# attiny85.net
KiCad netlist of a schematic drawn in EAGLE
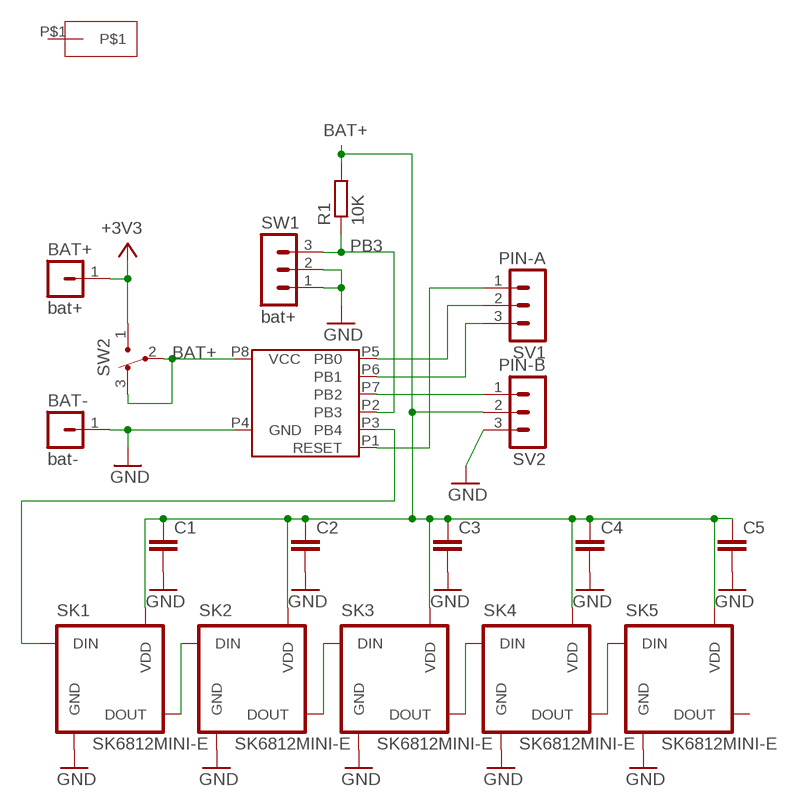
[diagram p0: schematic, sheet 1]

(export (version "E")
  (design (tool "Eeschema 10.0.6"))
  (components
    (comp (ref "ATTINY85-1")
      (value "ATTINY85")
      (footprint "eagle-import:ATTINY85-20SUR")
      (libsource (lib "eagle-import") (part "ATTINY85SOP8"))
    )
    (comp (ref "BAT+")
      (value "bat+")
      (footprint "eagle-import:PINHEAD-MA01-1")
      (libsource (lib "eagle-import") (part "PINHEAD-MA01-1"))
    )
    (comp (ref "BAT-")
      (value "bat-")
      (footprint "eagle-import:PINHEAD-MA01-1")
      (libsource (lib "eagle-import") (part "PINHEAD-MA01-1"))
    )
    (comp (ref "C1")
      (value "C-EUC2012")
      (footprint "eagle-import:C2012")
      (libsource (lib "eagle-import") (part "C-EUC2012"))
    )
    (comp (ref "C2")
      (value "C-EUC2012")
      (footprint "eagle-import:C2012")
      (libsource (lib "eagle-import") (part "C-EUC2012"))
    )
    (comp (ref "C3")
      (value "C-EUC2012")
      (footprint "eagle-import:C2012")
      (libsource (lib "eagle-import") (part "C-EUC2012"))
    )
    (comp (ref "C4")
      (value "C-EUC2012")
      (footprint "eagle-import:C2012")
      (libsource (lib "eagle-import") (part "C-EUC2012"))
    )
    (comp (ref "C5")
      (value "C-EUC2012")
      (footprint "eagle-import:C2012")
      (libsource (lib "eagle-import") (part "C-EUC2012"))
    )
    (comp (ref "PAD33")
      (value "PAD150X50")
      (footprint "eagle-import:PAD5X15")
      (libsource (lib "eagle-import") (part "PAD150X50"))
    )
    (comp (ref "R1")
      (value "10K")
      (footprint "eagle-import:M3216")
      (libsource (lib "eagle-import") (part "R-EU_M3216"))
    )
    (comp (ref "SK1")
      (value "SK6812MINI-E")
      (footprint "eagle-import:SK6812MINI-E")
      (libsource (lib "eagle-import") (part "SK6812MINI-E"))
    )
    (comp (ref "SK2")
      (value "SK6812MINI-E")
      (footprint "eagle-import:SK6812MINI-E")
      (libsource (lib "eagle-import") (part "SK6812MINI-E"))
    )
    (comp (ref "SK3")
      (value "SK6812MINI-E")
      (footprint "eagle-import:SK6812MINI-E")
      (libsource (lib "eagle-import") (part "SK6812MINI-E"))
    )
    (comp (ref "SK4")
      (value "SK6812MINI-E")
      (footprint "eagle-import:SK6812MINI-E")
      (libsource (lib "eagle-import") (part "SK6812MINI-E"))
    )
    (comp (ref "SK5")
      (value "SK6812MINI-E")
      (footprint "eagle-import:SK6812MINI-E")
      (libsource (lib "eagle-import") (part "SK6812MINI-E"))
    )
    (comp (ref "SV1")
      (value "PIN-A")
      (footprint "eagle-import:PINHEAD-MA03-1")
      (libsource (lib "eagle-import") (part "PINHEAD-MA03-1"))
    )
    (comp (ref "SV2")
      (value "PIN-B")
      (footprint "eagle-import:PINHEAD-MA03-1")
      (libsource (lib "eagle-import") (part "PINHEAD-MA03-1"))
    )
    (comp (ref "SW1")
      (value "bat+")
      (footprint "eagle-import:PINHEAD-MA03-1")
      (libsource (lib "eagle-import") (part "PINHEAD-MA03-1"))
    )
    (comp (ref "SW2")
      (value "POWER")
      (footprint "eagle-import:SW3-1")
      (fields (field (name "MF") "HiLetgo"))
      (libsource (lib "eagle-import") (part "SW3-1"))
    )
  )
  (nets
    (net (code "1") (name "+3V3") (class "Default")
      (node (ref "BAT+") (pin "1") (pinfunction "1_1") (pintype "passive"))
      (node (ref "SW2") (pin "1") (pinfunction "1_1") (pintype "passive"))
    )
    (net (code "2") (name "/BAT+") (class "Default")
      (node (ref "ATTINY85-1") (pin "P8") (pinfunction "VCC_P8") (pintype "bidirectional"))
      (node (ref "C1") (pin "1") (pinfunction "1_1") (pintype "passive"))
      (node (ref "C2") (pin "1") (pinfunction "1_1") (pintype "passive"))
      (node (ref "C3") (pin "1") (pinfunction "1_1") (pintype "passive"))
      (node (ref "C4") (pin "1") (pinfunction "1_1") (pintype "passive"))
      (node (ref "C5") (pin "1") (pinfunction "1_1") (pintype "passive"))
      (node (ref "R1") (pin "2") (pinfunction "2_2") (pintype "passive"))
      (node (ref "SK1") (pin "VDD") (pinfunction "VDD_VDD") (pintype "bidirectional"))
      (node (ref "SK2") (pin "VDD") (pinfunction "VDD_VDD") (pintype "bidirectional"))
      (node (ref "SK3") (pin "VDD") (pinfunction "VDD_VDD") (pintype "bidirectional"))
      (node (ref "SK4") (pin "VDD") (pinfunction "VDD_VDD") (pintype "bidirectional"))
      (node (ref "SK5") (pin "VDD") (pinfunction "VDD_VDD") (pintype "bidirectional"))
      (node (ref "SV2") (pin "2") (pinfunction "2_2") (pintype "passive"))
      (node (ref "SW2") (pin "2") (pinfunction "2_2") (pintype "passive"))
      (node (ref "SW2") (pin "3") (pinfunction "3_3") (pintype "passive"))
    )
    (net (code "3") (name "/PB3") (class "Default")
      (node (ref "ATTINY85-1") (pin "P2") (pinfunction "PB3_P2") (pintype "bidirectional"))
      (node (ref "R1") (pin "1") (pinfunction "1_1") (pintype "passive"))
      (node (ref "SW1") (pin "3") (pinfunction "3_3") (pintype "passive"))
    )
    (net (code "4") (name "GND") (class "Default")
      (node (ref "ATTINY85-1") (pin "P4") (pinfunction "GND_P4") (pintype "bidirectional"))
      (node (ref "BAT-") (pin "1") (pinfunction "1_1") (pintype "passive"))
      (node (ref "C1") (pin "2") (pinfunction "2_2") (pintype "passive"))
      (node (ref "C2") (pin "2") (pinfunction "2_2") (pintype "passive"))
      (node (ref "C3") (pin "2") (pinfunction "2_2") (pintype "passive"))
      (node (ref "C4") (pin "2") (pinfunction "2_2") (pintype "passive"))
      (node (ref "C5") (pin "2") (pinfunction "2_2") (pintype "passive"))
      (node (ref "SK1") (pin "GND") (pinfunction "GND_GND") (pintype "bidirectional"))
      (node (ref "SK2") (pin "GND") (pinfunction "GND_GND") (pintype "bidirectional"))
      (node (ref "SK3") (pin "GND") (pinfunction "GND_GND") (pintype "bidirectional"))
      (node (ref "SK4") (pin "GND") (pinfunction "GND_GND") (pintype "bidirectional"))
      (node (ref "SK5") (pin "GND") (pinfunction "GND_GND") (pintype "bidirectional"))
      (node (ref "SV2") (pin "3") (pinfunction "3_3") (pintype "passive"))
      (node (ref "SW1") (pin "1") (pinfunction "1_1") (pintype "passive"))
      (node (ref "SW1") (pin "2") (pinfunction "2_2") (pintype "passive"))
    )
    (net (code "5") (name "Net-(ATTINY85-1-PB0)") (class "Default")
      (node (ref "ATTINY85-1") (pin "P5") (pinfunction "PB0_P5") (pintype "bidirectional"))
      (node (ref "SV1") (pin "2") (pinfunction "2_2") (pintype "passive"))
    )
    (net (code "6") (name "Net-(ATTINY85-1-PB1)") (class "Default")
      (node (ref "ATTINY85-1") (pin "P6") (pinfunction "PB1_P6") (pintype "bidirectional"))
      (node (ref "SV1") (pin "3") (pinfunction "3_3") (pintype "passive"))
    )
    (net (code "7") (name "Net-(ATTINY85-1-PB2)") (class "Default")
      (node (ref "ATTINY85-1") (pin "P7") (pinfunction "PB2_P7") (pintype "bidirectional"))
      (node (ref "SV2") (pin "1") (pinfunction "1_1") (pintype "passive"))
    )
    (net (code "8") (name "Net-(ATTINY85-1-PB4)") (class "Default")
      (node (ref "ATTINY85-1") (pin "P3") (pinfunction "PB4_P3") (pintype "bidirectional"))
      (node (ref "SK1") (pin "DIN") (pinfunction "DIN_DIN") (pintype "input"))
    )
    (net (code "9") (name "Net-(ATTINY85-1-RESET)") (class "Default")
      (node (ref "ATTINY85-1") (pin "P1") (pinfunction "RESET_P1") (pintype "bidirectional"))
      (node (ref "SV1") (pin "1") (pinfunction "1_1") (pintype "passive"))
    )
    (net (code "10") (name "Net-(SK1-PadDOUT)") (class "Default")
      (node (ref "SK1") (pin "DOUT") (pinfunction "DOUT_DOUT") (pintype "output"))
      (node (ref "SK2") (pin "DIN") (pinfunction "DIN_DIN") (pintype "input"))
    )
    (net (code "11") (name "Net-(SK2-PadDOUT)") (class "Default")
      (node (ref "SK2") (pin "DOUT") (pinfunction "DOUT_DOUT") (pintype "output"))
      (node (ref "SK3") (pin "DIN") (pinfunction "DIN_DIN") (pintype "input"))
    )
    (net (code "12") (name "Net-(SK3-PadDOUT)") (class "Default")
      (node (ref "SK3") (pin "DOUT") (pinfunction "DOUT_DOUT") (pintype "output"))
      (node (ref "SK4") (pin "DIN") (pinfunction "DIN_DIN") (pintype "input"))
    )
    (net (code "13") (name "Net-(SK4-PadDOUT)") (class "Default")
      (node (ref "SK4") (pin "DOUT") (pinfunction "DOUT_DOUT") (pintype "output"))
      (node (ref "SK5") (pin "DIN") (pinfunction "DIN_DIN") (pintype "input"))
    )
    (net (code "14") (name "unconnected-(PAD33-PadP$1)") (class "Default")
      (node (ref "PAD33") (pin "P$1") (pinfunction "P$1_P$1") (pintype "bidirectional"))
    )
    (net (code "15") (name "unconnected-(SK5-PadDOUT)") (class "Default")
      (node (ref "SK5") (pin "DOUT") (pinfunction "DOUT_DOUT") (pintype "output"))
    )
  )
)
